# WCRL_Board_V2.net
KiCad netlist of a schematic drawn in EAGLE
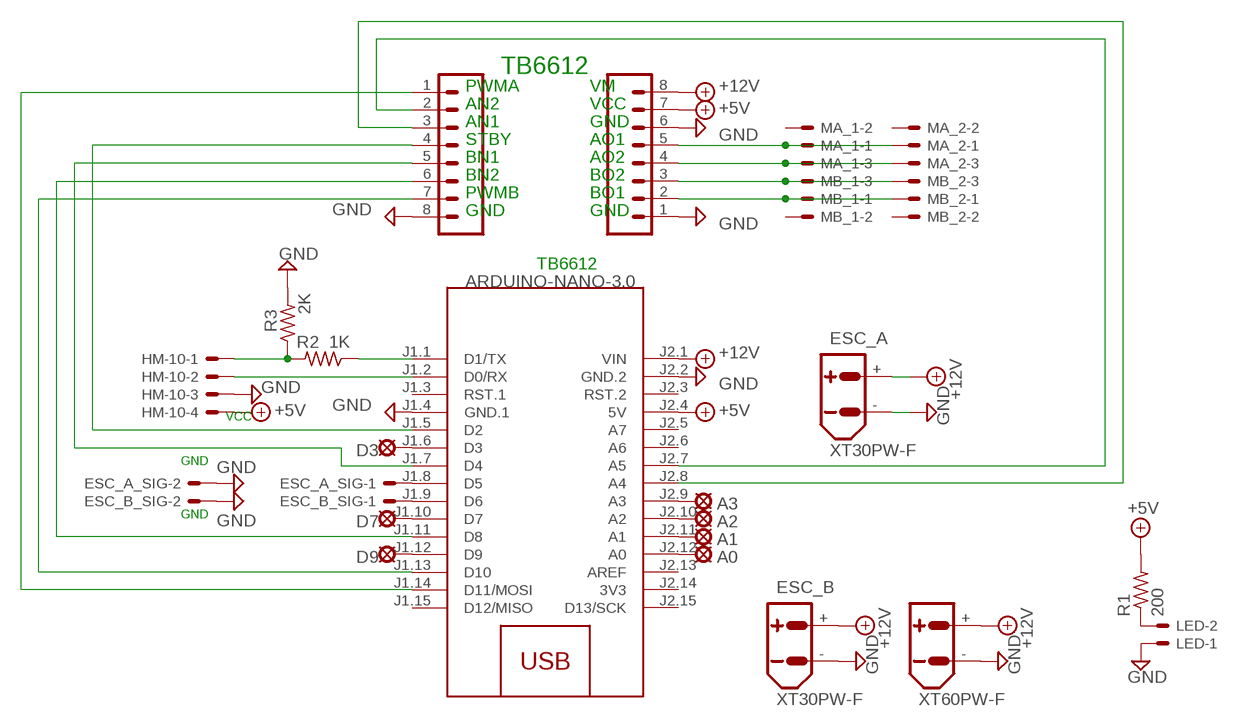
[diagram p0: schematic, sheet 1]

(export (version "E")
  (design (tool "Eeschema 10.0.6"))
  (components
    (comp (ref "A0")
      (value "LSP10")
      (footprint "eagle-import:LSP10")
      (libsource (lib "eagle-import") (part "LSP10"))
    )
    (comp (ref "A1")
      (value "LSP10")
      (footprint "eagle-import:LSP10")
      (libsource (lib "eagle-import") (part "LSP10"))
    )
    (comp (ref "A2")
      (value "LSP10")
      (footprint "eagle-import:LSP10")
      (libsource (lib "eagle-import") (part "LSP10"))
    )
    (comp (ref "A3")
      (value "LSP10")
      (footprint "eagle-import:LSP10")
      (libsource (lib "eagle-import") (part "LSP10"))
    )
    (comp (ref "BATTERY")
      (value "XT60PW-F")
      (footprint "eagle-import:XT60PW-F")
      (libsource (lib "eagle-import") (part "XT60PW-F"))
    )
    (comp (ref "D3")
      (value "LSP10")
      (footprint "eagle-import:LSP10")
      (libsource (lib "eagle-import") (part "LSP10"))
    )
    (comp (ref "D7")
      (value "LSP10")
      (footprint "eagle-import:LSP10")
      (libsource (lib "eagle-import") (part "LSP10"))
    )
    (comp (ref "D9")
      (value "LSP10")
      (footprint "eagle-import:LSP10")
      (libsource (lib "eagle-import") (part "LSP10"))
    )
    (comp (ref "ESC_A")
      (value "XT30PW-F")
      (footprint "eagle-import:XT30PW-F")
      (libsource (lib "eagle-import") (part "XT30PW-F"))
    )
    (comp (ref "ESC_A_SIG")
      (value "JST-XH-02-PIN-LONG-PAD")
      (footprint "eagle-import:JST-XH-02-PACKAGE-LONG-PAD")
      (libsource (lib "eagle-import") (part "JST-XH-02-PIN-LONG-PAD"))
    )
    (comp (ref "ESC_B")
      (value "XT30PW-F")
      (footprint "eagle-import:XT30PW-F")
      (libsource (lib "eagle-import") (part "XT30PW-F"))
    )
    (comp (ref "ESC_B_SIG")
      (value "JST-XH-02-PIN-LONG-PAD")
      (footprint "eagle-import:JST-XH-02-PACKAGE-LONG-PAD")
      (libsource (lib "eagle-import") (part "JST-XH-02-PIN-LONG-PAD"))
    )
    (comp (ref "HM-10")
      (value "JST-XH-04-PIN-LONG-PAD")
      (footprint "eagle-import:JST-XH-04-PACKAGE-LONG-PAD")
      (libsource (lib "eagle-import") (part "JST-XH-04-PIN-LONG-PAD"))
    )
    (comp (ref "J1")
      (value "CONN_08NO_SILK_FEMALE_PTH")
      (footprint "eagle-import:1X08_NO_SILK")
      (libsource (lib "eagle-import") (part "CONN_08NO_SILK_FEMALE_PTH"))
    )
    (comp (ref "J2")
      (value "CONN_08NO_SILK_FEMALE_PTH")
      (footprint "eagle-import:1X08_NO_SILK")
      (libsource (lib "eagle-import") (part "CONN_08NO_SILK_FEMALE_PTH"))
    )
    (comp (ref "LED")
      (value "JST-XH-02-PIN-LONG-PAD")
      (footprint "eagle-import:JST-XH-02-PACKAGE-LONG-PAD")
      (libsource (lib "eagle-import") (part "JST-XH-02-PIN-LONG-PAD"))
    )
    (comp (ref "M1")
      (value "ARDUINO-NANO-3.0")
      (footprint "eagle-import:ARDUINO-NANO-3.0")
      (libsource (lib "eagle-import") (part "ARDUINO-NANO-3.0"))
    )
    (comp (ref "MA_1")
      (value "JST-XH-03-PIN-LONG-PAD")
      (footprint "eagle-import:JST-XH-03-PACKAGE-LONG-PAD")
      (libsource (lib "eagle-import") (part "JST-XH-03-PIN-LONG-PAD"))
    )
    (comp (ref "MA_2")
      (value "JST-XH-03-PIN-LONG-PAD")
      (footprint "eagle-import:JST-XH-03-PACKAGE-LONG-PAD")
      (libsource (lib "eagle-import") (part "JST-XH-03-PIN-LONG-PAD"))
    )
    (comp (ref "MB_1")
      (value "JST-XH-03-PIN-LONG-PAD")
      (footprint "eagle-import:JST-XH-03-PACKAGE-LONG-PAD")
      (libsource (lib "eagle-import") (part "JST-XH-03-PIN-LONG-PAD"))
    )
    (comp (ref "MB_2")
      (value "JST-XH-03-PIN-LONG-PAD")
      (footprint "eagle-import:JST-XH-03-PACKAGE-LONG-PAD")
      (libsource (lib "eagle-import") (part "JST-XH-03-PIN-LONG-PAD"))
    )
    (comp (ref "R1")
      (value "200")
      (footprint "eagle-import:0204_5")
      (libsource (lib "eagle-import") (part "R-US_0204/5"))
    )
    (comp (ref "R2")
      (value "1K")
      (footprint "eagle-import:0204_5")
      (libsource (lib "eagle-import") (part "R-US_0204/5"))
    )
    (comp (ref "R3")
      (value "2K")
      (footprint "eagle-import:0204_5")
      (libsource (lib "eagle-import") (part "R-US_0204/5"))
    )
  )
  (nets
    (net (code "1") (name "+5V") (class "Default")
      (node (ref "HM-10") (pin "4") (pinfunction "S_4") (pintype "passive"))
      (node (ref "J1") (pin "7") (pinfunction "7_7") (pintype "passive"))
      (node (ref "M1") (pin "J2.4") (pinfunction "5V_J2.4") (pintype "power_in"))
      (node (ref "R1") (pin "2") (pinfunction "2_2") (pintype "passive"))
    )
    (net (code "2") (name "+12V") (class "Default")
      (node (ref "BATTERY") (pin "+") (pinfunction "+_+") (pintype "power_in"))
      (node (ref "ESC_A") (pin "+") (pinfunction "+_+") (pintype "power_in"))
      (node (ref "ESC_B") (pin "+") (pinfunction "+_+") (pintype "power_in"))
      (node (ref "J1") (pin "8") (pinfunction "8_8") (pintype "passive"))
      (node (ref "M1") (pin "J2.1") (pinfunction "VIN_J2.1") (pintype "power_in"))
    )
    (net (code "3") (name "/3V3") (class "Default")
      (node (ref "M1") (pin "J2.14") (pinfunction "3V3_J2.14") (pintype "power_in"))
    )
    (net (code "4") (name "GND") (class "Default")
      (node (ref "BATTERY") (pin "-") (pinfunction "-_-") (pintype "power_in"))
      (node (ref "ESC_A") (pin "-") (pinfunction "-_-") (pintype "power_in"))
      (node (ref "ESC_A_SIG") (pin "2") (pinfunction "S_2") (pintype "passive"))
      (node (ref "ESC_B") (pin "-") (pinfunction "-_-") (pintype "power_in"))
      (node (ref "ESC_B_SIG") (pin "2") (pinfunction "S_2") (pintype "passive"))
      (node (ref "HM-10") (pin "3") (pinfunction "S_3") (pintype "passive"))
      (node (ref "J1") (pin "1") (pinfunction "1_1") (pintype "passive"))
      (node (ref "J1") (pin "6") (pinfunction "6_6") (pintype "passive"))
      (node (ref "J2") (pin "8") (pinfunction "8_8") (pintype "passive"))
      (node (ref "LED") (pin "1") (pinfunction "S_1") (pintype "passive"))
      (node (ref "M1") (pin "J1.4") (pinfunction "GND.1_J1.4") (pintype "power_in"))
      (node (ref "M1") (pin "J2.2") (pinfunction "GND.2_J2.2") (pintype "power_in"))
      (node (ref "R3") (pin "2") (pinfunction "2_2") (pintype "passive"))
    )
    (net (code "5") (name "Net-(ESC_A_SIGA-S)") (class "Default")
      (node (ref "ESC_A_SIG") (pin "1") (pinfunction "S_1") (pintype "passive"))
      (node (ref "M1") (pin "J1.8") (pinfunction "D5_J1.8") (pintype "bidirectional"))
    )
    (net (code "6") (name "Net-(ESC_B_SIGA-S)") (class "Default")
      (node (ref "ESC_B_SIG") (pin "1") (pinfunction "S_1") (pintype "passive"))
      (node (ref "M1") (pin "J1.9") (pinfunction "D6_J1.9") (pintype "bidirectional"))
    )
    (net (code "7") (name "Net-(HM-10A-S)") (class "Default")
      (node (ref "HM-10") (pin "1") (pinfunction "S_1") (pintype "passive"))
      (node (ref "R2") (pin "2") (pinfunction "2_2") (pintype "passive"))
      (node (ref "R3") (pin "1") (pinfunction "1_1") (pintype "passive"))
    )
    (net (code "8") (name "Net-(HM-10B-S)") (class "Default")
      (node (ref "HM-10") (pin "2") (pinfunction "S_2") (pintype "passive"))
      (node (ref "M1") (pin "J1.2") (pinfunction "D0/RX_J1.2") (pintype "bidirectional"))
    )
    (net (code "9") (name "Net-(LEDB-S)") (class "Default")
      (node (ref "LED") (pin "2") (pinfunction "S_2") (pintype "passive"))
      (node (ref "R1") (pin "1") (pinfunction "1_1") (pintype "passive"))
    )
    (net (code "10") (name "Net-(M1-A0)") (class "Default")
      (node (ref "A0") (pin "MP") (pinfunction "MP_MP") (pintype "passive"))
      (node (ref "M1") (pin "J2.12") (pinfunction "A0_J2.12") (pintype "bidirectional"))
    )
    (net (code "11") (name "Net-(M1-A1)") (class "Default")
      (node (ref "A1") (pin "MP") (pinfunction "MP_MP") (pintype "passive"))
      (node (ref "M1") (pin "J2.11") (pinfunction "A1_J2.11") (pintype "bidirectional"))
    )
    (net (code "12") (name "Net-(M1-A2)") (class "Default")
      (node (ref "A2") (pin "MP") (pinfunction "MP_MP") (pintype "passive"))
      (node (ref "M1") (pin "J2.10") (pinfunction "A2_J2.10") (pintype "bidirectional"))
    )
    (net (code "13") (name "Net-(M1-A3)") (class "Default")
      (node (ref "A3") (pin "MP") (pinfunction "MP_MP") (pintype "passive"))
      (node (ref "M1") (pin "J2.9") (pinfunction "A3_J2.9") (pintype "bidirectional"))
    )
    (net (code "14") (name "Net-(M1-A4)") (class "Default")
      (node (ref "J2") (pin "3") (pinfunction "3_3") (pintype "passive"))
      (node (ref "M1") (pin "J2.8") (pinfunction "A4_J2.8") (pintype "bidirectional"))
    )
    (net (code "15") (name "Net-(M1-A5)") (class "Default")
      (node (ref "J2") (pin "2") (pinfunction "2_2") (pintype "passive"))
      (node (ref "M1") (pin "J2.7") (pinfunction "A5_J2.7") (pintype "bidirectional"))
    )
    (net (code "16") (name "Net-(M1-D1{slash}TX)") (class "Default")
      (node (ref "M1") (pin "J1.1") (pinfunction "D1/TX_J1.1") (pintype "bidirectional"))
      (node (ref "R2") (pin "1") (pinfunction "1_1") (pintype "passive"))
    )
    (net (code "17") (name "Net-(M1-D2)") (class "Default")
      (node (ref "J2") (pin "4") (pinfunction "4_4") (pintype "passive"))
      (node (ref "M1") (pin "J1.5") (pinfunction "D2_J1.5") (pintype "bidirectional"))
    )
    (net (code "18") (name "Net-(M1-D3)") (class "Default")
      (node (ref "D3") (pin "MP") (pinfunction "MP_MP") (pintype "passive"))
      (node (ref "M1") (pin "J1.6") (pinfunction "D3_J1.6") (pintype "bidirectional"))
    )
    (net (code "19") (name "Net-(M1-D4)") (class "Default")
      (node (ref "J2") (pin "5") (pinfunction "5_5") (pintype "passive"))
      (node (ref "M1") (pin "J1.7") (pinfunction "D4_J1.7") (pintype "bidirectional"))
    )
    (net (code "20") (name "Net-(M1-D7)") (class "Default")
      (node (ref "D7") (pin "MP") (pinfunction "MP_MP") (pintype "passive"))
      (node (ref "M1") (pin "J1.10") (pinfunction "D7_J1.10") (pintype "bidirectional"))
    )
    (net (code "21") (name "Net-(M1-D8)") (class "Default")
      (node (ref "J2") (pin "6") (pinfunction "6_6") (pintype "passive"))
      (node (ref "M1") (pin "J1.11") (pinfunction "D8_J1.11") (pintype "bidirectional"))
    )
    (net (code "22") (name "Net-(M1-D9)") (class "Default")
      (node (ref "D9") (pin "MP") (pinfunction "MP_MP") (pintype "passive"))
      (node (ref "M1") (pin "J1.12") (pinfunction "D9_J1.12") (pintype "bidirectional"))
    )
    (net (code "23") (name "Net-(M1-D10)") (class "Default")
      (node (ref "J2") (pin "7") (pinfunction "7_7") (pintype "passive"))
      (node (ref "M1") (pin "J1.13") (pinfunction "D10_J1.13") (pintype "bidirectional"))
    )
    (net (code "24") (name "Net-(M1-D11{slash}MOSI)") (class "Default")
      (node (ref "J2") (pin "1") (pinfunction "1_1") (pintype "passive"))
      (node (ref "M1") (pin "J1.14") (pinfunction "D11/MOSI_J1.14") (pintype "bidirectional"))
    )
    (net (code "25") (name "Net-(MA_1A-S)") (class "Default")
      (node (ref "J1") (pin "5") (pinfunction "5_5") (pintype "passive"))
      (node (ref "MA_1") (pin "1") (pinfunction "S_1") (pintype "passive"))
      (node (ref "MA_2") (pin "1") (pinfunction "S_1") (pintype "passive"))
    )
    (net (code "26") (name "Net-(MA_1C-S)") (class "Default")
      (node (ref "J1") (pin "4") (pinfunction "4_4") (pintype "passive"))
      (node (ref "MA_1") (pin "3") (pinfunction "S_3") (pintype "passive"))
      (node (ref "MA_2") (pin "3") (pinfunction "S_3") (pintype "passive"))
    )
    (net (code "27") (name "Net-(MB_1A-S)") (class "Default")
      (node (ref "J1") (pin "2") (pinfunction "2_2") (pintype "passive"))
      (node (ref "MB_1") (pin "1") (pinfunction "S_1") (pintype "passive"))
      (node (ref "MB_2") (pin "1") (pinfunction "S_1") (pintype "passive"))
    )
    (net (code "28") (name "Net-(MB_1C-S)") (class "Default")
      (node (ref "J1") (pin "3") (pinfunction "3_3") (pintype "passive"))
      (node (ref "MB_1") (pin "3") (pinfunction "S_3") (pintype "passive"))
      (node (ref "MB_2") (pin "3") (pinfunction "S_3") (pintype "passive"))
    )
    (net (code "29") (name "unconnected-(M1-A6-PadJ2.6)") (class "Default")
      (node (ref "M1") (pin "J2.6") (pinfunction "A6_J2.6") (pintype "bidirectional"))
    )
    (net (code "30") (name "unconnected-(M1-A7-PadJ2.5)") (class "Default")
      (node (ref "M1") (pin "J2.5") (pinfunction "A7_J2.5") (pintype "bidirectional"))
    )
    (net (code "31") (name "unconnected-(M1-AREF-PadJ2.13)") (class "Default")
      (node (ref "M1") (pin "J2.13") (pinfunction "AREF_J2.13") (pintype "bidirectional"))
    )
    (net (code "32") (name "unconnected-(M1-D12{slash}MISO-PadJ1.15)") (class "Default")
      (node (ref "M1") (pin "J1.15") (pinfunction "D12/MISO_J1.15") (pintype "bidirectional"))
    )
    (net (code "33") (name "unconnected-(M1-D13{slash}SCK-PadJ2.15)") (class "Default")
      (node (ref "M1") (pin "J2.15") (pinfunction "D13/SCK_J2.15") (pintype "bidirectional"))
    )
    (net (code "34") (name "unconnected-(M1-RST.1-PadJ1.3)") (class "Default")
      (node (ref "M1") (pin "J1.3") (pinfunction "RST.1_J1.3") (pintype "bidirectional"))
    )
    (net (code "35") (name "unconnected-(M1-RST.2-PadJ2.3)") (class "Default")
      (node (ref "M1") (pin "J2.3") (pinfunction "RST.2_J2.3") (pintype "bidirectional"))
    )
    (net (code "36") (name "unconnected-(MA_1B-S-Pad2)") (class "Default")
      (node (ref "MA_1") (pin "2") (pinfunction "S_2") (pintype "passive"))
    )
    (net (code "37") (name "unconnected-(MA_2B-S-Pad2)") (class "Default")
      (node (ref "MA_2") (pin "2") (pinfunction "S_2") (pintype "passive"))
    )
    (net (code "38") (name "unconnected-(MB_1B-S-Pad2)") (class "Default")
      (node (ref "MB_1") (pin "2") (pinfunction "S_2") (pintype "passive"))
    )
    (net (code "39") (name "unconnected-(MB_2B-S-Pad2)") (class "Default")
      (node (ref "MB_2") (pin "2") (pinfunction "S_2") (pintype "passive"))
    )
  )
)
